# 17.net
KiCad netlist of a schematic drawn in Altium Designer
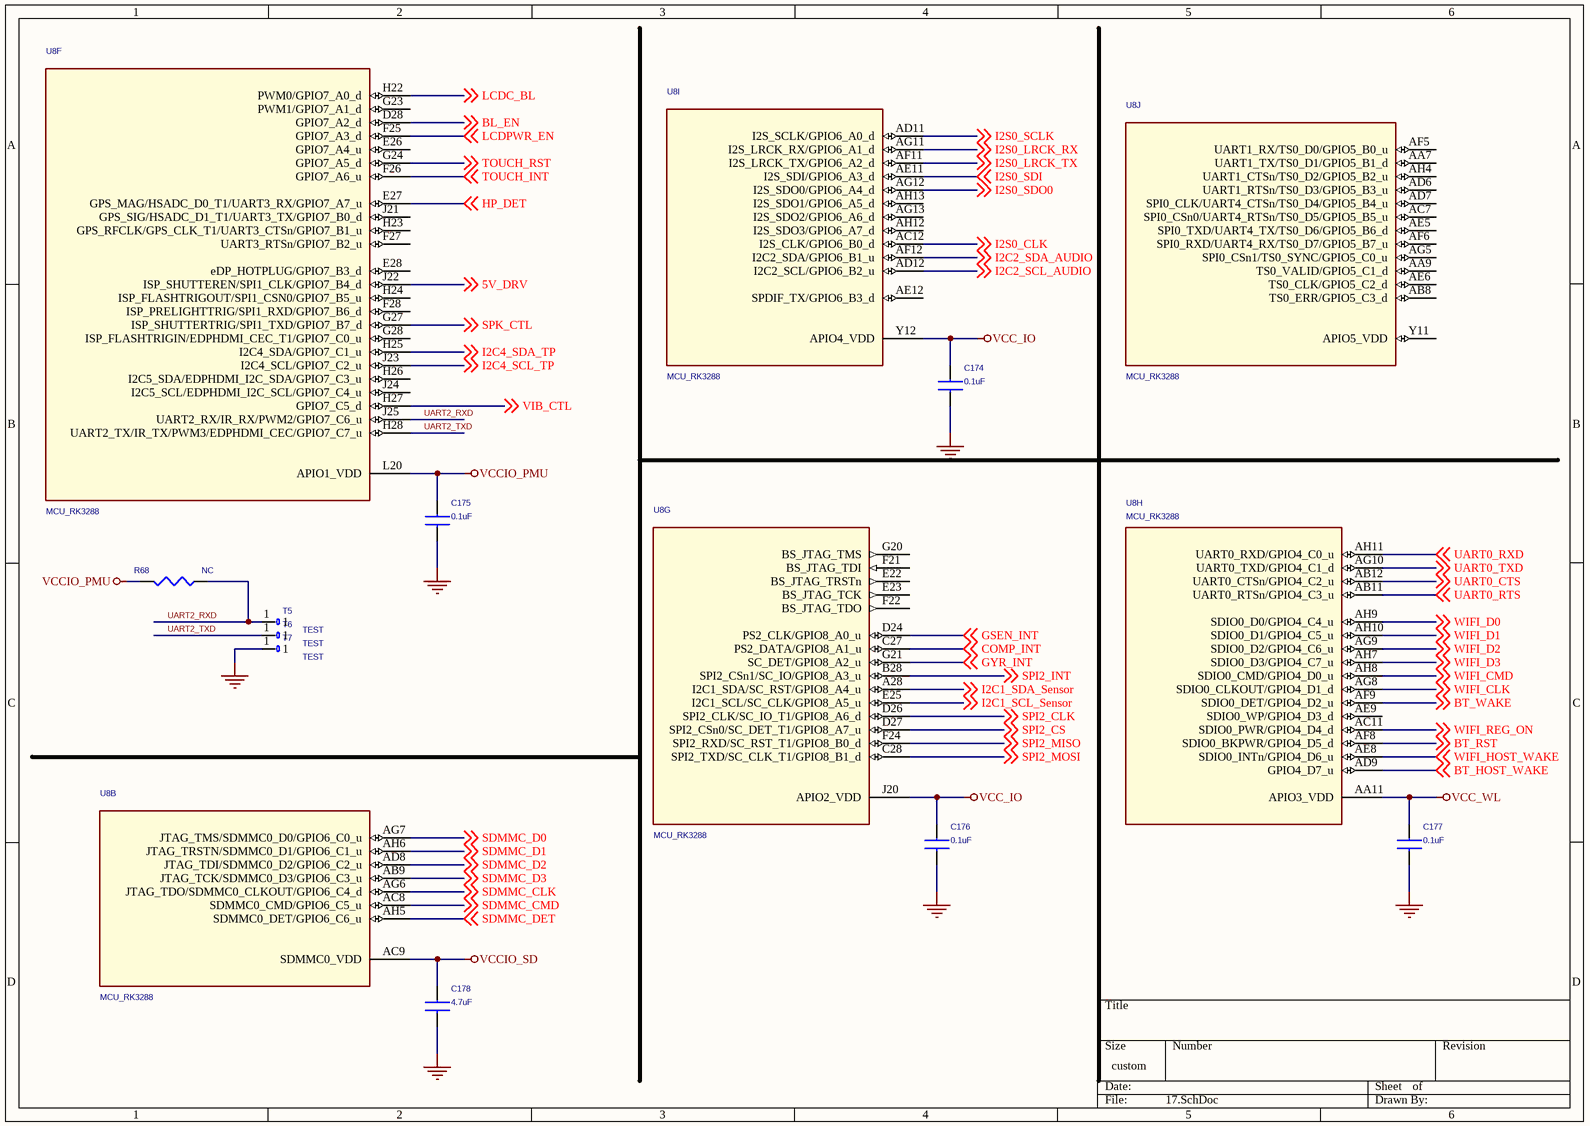
[diagram p0: 17.SchDoc]

(export (version "E")
  (design (tool "Eeschema 10.0.6"))
  (components
    (comp (ref "C174")
      (value "0.1uF")
      (footprint "C0603")
      (description "CAP,MLCC,100nF,+/-10%,X7R,6.3V,SMD0402")
      (libsource (lib "*") (part "CAP NP_Dup3"))
    )
    (comp (ref "C175")
      (value "0.1uF")
      (footprint "C0603")
      (description "CAP,MLCC,100nF,+/-10%,X7R,6.3V,SMD0402")
      (libsource (lib "*") (part "CAP NP_Dup3"))
    )
    (comp (ref "C176") (value "0.1uF") (footprint "C0603") (libsource (lib "*") (part "CAP NP_Dup3")))
    (comp (ref "C177")
      (value "0.1uF")
      (footprint "C0603")
      (description "CAP,MLCC,100nF,+/-10%,X7R,6.3V,SMD0402")
      (libsource (lib "*") (part "CAP NP_Dup3"))
    )
    (comp (ref "C178")
      (value "4.7uF")
      (footprint "C0603")
      (description "CAP,MLCC,100nF,+/-10%,X7R,6.3V,SMD0402")
      (libsource (lib "*") (part "CAP NP_Dup3"))
    )
    (comp (ref "R68")
      (value "NC")
      (footprint "r0402")
      (description "RES,thick film,10KOhm,+/-5%,1/16W,SMD0402")
      (libsource (lib "*") (part "RESISTOR_0_Dup3"))
    )
    (comp (ref "T5") (value "TEST") (footprint "TEST") (libsource (lib "*") (part "TEST_0")))
    (comp (ref "T6") (value "TEST") (footprint "TEST") (libsource (lib "*") (part "TEST_0")))
    (comp (ref "T7") (value "TEST") (footprint "TEST") (libsource (lib "*") (part "TEST_0")))
    (comp (ref "U8")
      (value "MCU_RK3288")
      (footprint "BGA453-19X19")
      (libsource (lib "*") (part "MCU_RK3288_3"))
    )
  )
  (nets
    (net (code "1") (name "/UART2_RXD") (class "Default")
      (node (ref "R68") (pin "1") (pinfunction "1_1") (pintype "passive"))
      (node (ref "T5") (pin "1") (pinfunction "1_1") (pintype "passive"))
      (node (ref "U8") (pin "J25") (pinfunction "UART2_RX/IR_RX/PWM2/GPIO7_C6_u_J25") (pintype "bidirectional"))
    )
    (net (code "2") (name "/UART2_TXD") (class "Default")
      (node (ref "T6") (pin "1") (pinfunction "1_1") (pintype "passive"))
      (node (ref "U8") (pin "H28") (pinfunction "UART2_TX/IR_TX/PWM3/EDPHDMI_CEC/GPIO7_C7_u_H28") (pintype "bidirectional"))
    )
    (net (code "3") (name "5V_DRV") (class "Default")
      (node (ref "U8") (pin "J22") (pinfunction "ISP_SHUTTEREN/SPI1_CLK/GPIO7_B4_d_J22") (pintype "bidirectional"))
    )
    (net (code "4") (name "BL_EN") (class "Default")
      (node (ref "U8") (pin "D28") (pinfunction "GPIO7_A2_d_D28") (pintype "bidirectional"))
    )
    (net (code "5") (name "BT_HOST_WAKE") (class "Default")
      (node (ref "U8") (pin "AD9") (pinfunction "GPIO4_D7_u_AD9") (pintype "bidirectional"))
    )
    (net (code "6") (name "BT_RST") (class "Default")
      (node (ref "U8") (pin "AF8") (pinfunction "SDIO0_BKPWR/GPIO4_D5_d_AF8") (pintype "bidirectional"))
    )
    (net (code "7") (name "BT_WAKE") (class "Default")
      (node (ref "U8") (pin "AF9") (pinfunction "SDIO0_DET/GPIO4_D2_u_AF9") (pintype "bidirectional"))
    )
    (net (code "8") (name "COMP_INT") (class "Default")
      (node (ref "U8") (pin "C27") (pinfunction "PS2_DATA/GPIO8_A1_u_C27") (pintype "bidirectional"))
    )
    (net (code "9") (name "GND") (class "Default")
      (node (ref "C174") (pin "1") (pinfunction "1_1") (pintype "passive"))
      (node (ref "C175") (pin "1") (pinfunction "1_1") (pintype "passive"))
      (node (ref "C176") (pin "2") (pinfunction "2_2") (pintype "passive"))
      (node (ref "C177") (pin "1") (pinfunction "1_1") (pintype "passive"))
      (node (ref "C178") (pin "2") (pinfunction "2_2") (pintype "passive"))
      (node (ref "T7") (pin "1") (pinfunction "1_1") (pintype "passive"))
    )
    (net (code "10") (name "GSEN_INT") (class "Default")
      (node (ref "U8") (pin "D24") (pinfunction "PS2_CLK/GPIO8_A0_u_D24") (pintype "bidirectional"))
    )
    (net (code "11") (name "GYR_INT") (class "Default")
      (node (ref "U8") (pin "G21") (pinfunction "SC_DET/GPIO8_A2_u_G21") (pintype "bidirectional"))
    )
    (net (code "12") (name "HP_DET") (class "Default")
      (node (ref "U8") (pin "E27") (pinfunction "GPS_MAG/HSADC_D0_T1/UART3_RX/GPIO7_A7_u_E27") (pintype "bidirectional"))
    )
    (net (code "13") (name "I2C1_SCL_Sensor") (class "Default")
      (node (ref "U8") (pin "E25") (pinfunction "I2C1_SCL/SC_CLK/GPIO8_A5_u_E25") (pintype "bidirectional"))
    )
    (net (code "14") (name "I2C1_SDA_Sensor") (class "Default")
      (node (ref "U8") (pin "A28") (pinfunction "I2C1_SDA/SC_RST/GPIO8_A4_u_A28") (pintype "bidirectional"))
    )
    (net (code "15") (name "I2C2_SCL_AUDIO") (class "Default")
      (node (ref "U8") (pin "AD12") (pinfunction "I2C2_SCL/GPIO6_B2_u_AD12") (pintype "bidirectional"))
    )
    (net (code "16") (name "I2C2_SDA_AUDIO") (class "Default")
      (node (ref "U8") (pin "AF12") (pinfunction "I2C2_SDA/GPIO6_B1_u_AF12") (pintype "bidirectional"))
    )
    (net (code "17") (name "I2C4_SCL_TP") (class "Default")
      (node (ref "U8") (pin "J23") (pinfunction "I2C4_SCL/GPIO7_C2_u_J23") (pintype "bidirectional"))
    )
    (net (code "18") (name "I2C4_SDA_TP") (class "Default")
      (node (ref "U8") (pin "H25") (pinfunction "I2C4_SDA/GPIO7_C1_u_H25") (pintype "bidirectional"))
    )
    (net (code "19") (name "I2S0_CLK") (class "Default")
      (node (ref "U8") (pin "AC12") (pinfunction "I2S_CLK/GPIO6_B0_d_AC12") (pintype "bidirectional"))
    )
    (net (code "20") (name "I2S0_LRCK_RX") (class "Default")
      (node (ref "U8") (pin "AG11") (pinfunction "I2S_LRCK_RX/GPIO6_A1_d_AG11") (pintype "bidirectional"))
    )
    (net (code "21") (name "I2S0_LRCK_TX") (class "Default")
      (node (ref "U8") (pin "AF11") (pinfunction "I2S_LRCK_TX/GPIO6_A2_d_AF11") (pintype "bidirectional"))
    )
    (net (code "22") (name "I2S0_SCLK") (class "Default")
      (node (ref "U8") (pin "AD11") (pinfunction "I2S_SCLK/GPIO6_A0_d_AD11") (pintype "bidirectional"))
    )
    (net (code "23") (name "I2S0_SDI") (class "Default")
      (node (ref "U8") (pin "AE11") (pinfunction "I2S_SDI/GPIO6_A3_d_AE11") (pintype "bidirectional"))
    )
    (net (code "24") (name "I2S0_SDO0") (class "Default")
      (node (ref "U8") (pin "AG12") (pinfunction "I2S_SDO0/GPIO6_A4_d_AG12") (pintype "bidirectional"))
    )
    (net (code "25") (name "LCDC_BL") (class "Default")
      (node (ref "U8") (pin "H22") (pinfunction "PWM0/GPIO7_A0_d_H22") (pintype "bidirectional"))
    )
    (net (code "26") (name "LCDPWR_EN") (class "Default")
      (node (ref "U8") (pin "F25") (pinfunction "GPIO7_A3_d_F25") (pintype "bidirectional"))
    )
    (net (code "27") (name "SDMMC_CLK") (class "Default")
      (node (ref "U8") (pin "AG6") (pinfunction "JTAG_TDO/SDMMC0_CLKOUT/GPIO6_C4_d_AG6") (pintype "bidirectional"))
    )
    (net (code "28") (name "SDMMC_CMD") (class "Default")
      (node (ref "U8") (pin "AC8") (pinfunction "SDMMC0_CMD/GPIO6_C5_u_AC8") (pintype "bidirectional"))
    )
    (net (code "29") (name "SDMMC_D0") (class "Default")
      (node (ref "U8") (pin "AG7") (pinfunction "JTAG_TMS/SDMMC0_D0/GPIO6_C0_u_AG7") (pintype "bidirectional"))
    )
    (net (code "30") (name "SDMMC_D1") (class "Default")
      (node (ref "U8") (pin "AH6") (pinfunction "JTAG_TRSTN/SDMMC0_D1/GPIO6_C1_u_AH6") (pintype "bidirectional"))
    )
    (net (code "31") (name "SDMMC_D2") (class "Default")
      (node (ref "U8") (pin "AD8") (pinfunction "JTAG_TDI/SDMMC0_D2/GPIO6_C2_u_AD8") (pintype "bidirectional"))
    )
    (net (code "32") (name "SDMMC_D3") (class "Default")
      (node (ref "U8") (pin "AB9") (pinfunction "JTAG_TCK/SDMMC0_D3/GPIO6_C3_u_AB9") (pintype "bidirectional"))
    )
    (net (code "33") (name "SDMMC_DET") (class "Default")
      (node (ref "U8") (pin "AH5") (pinfunction "SDMMC0_DET/GPIO6_C6_u_AH5") (pintype "bidirectional"))
    )
    (net (code "34") (name "SPI2_CLK") (class "Default")
      (node (ref "U8") (pin "D26") (pinfunction "SPI2_CLK/SC_IO_T1/GPIO8_A6_d_D26") (pintype "bidirectional"))
    )
    (net (code "35") (name "SPI2_CS") (class "Default")
      (node (ref "U8") (pin "D27") (pinfunction "SPI2_CSn0/SC_DET_T1/GPIO8_A7_u_D27") (pintype "bidirectional"))
    )
    (net (code "36") (name "SPI2_INT") (class "Default")
      (node (ref "U8") (pin "B28") (pinfunction "SPI2_CSn1/SC_IO/GPIO8_A3_u_B28") (pintype "bidirectional"))
    )
    (net (code "37") (name "SPI2_MISO") (class "Default")
      (node (ref "U8") (pin "F24") (pinfunction "SPI2_RXD/SC_RST_T1/GPIO8_B0_d_F24") (pintype "bidirectional"))
    )
    (net (code "38") (name "SPI2_MOSI") (class "Default")
      (node (ref "U8") (pin "C28") (pinfunction "SPI2_TXD/SC_CLK_T1/GPIO8_B1_d_C28") (pintype "bidirectional"))
    )
    (net (code "39") (name "SPK_CTL") (class "Default")
      (node (ref "U8") (pin "G27") (pinfunction "ISP_SHUTTERTRIG/SPI1_TXD/GPIO7_B7_d_G27") (pintype "bidirectional"))
    )
    (net (code "40") (name "TOUCH_INT") (class "Default")
      (node (ref "U8") (pin "F26") (pinfunction "GPIO7_A6_u_F26") (pintype "bidirectional"))
    )
    (net (code "41") (name "TOUCH_RST") (class "Default")
      (node (ref "U8") (pin "G24") (pinfunction "GPIO7_A5_d_G24") (pintype "bidirectional"))
    )
    (net (code "42") (name "UART0_CTS") (class "Default")
      (node (ref "U8") (pin "AB12") (pinfunction "UART0_CTSn/GPIO4_C2_u_AB12") (pintype "bidirectional"))
    )
    (net (code "43") (name "UART0_RTS") (class "Default")
      (node (ref "U8") (pin "AB11") (pinfunction "UART0_RTSn/GPIO4_C3_u_AB11") (pintype "bidirectional"))
    )
    (net (code "44") (name "UART0_RXD") (class "Default")
      (node (ref "U8") (pin "AH11") (pinfunction "UART0_RXD/GPIO4_C0_u_AH11") (pintype "bidirectional"))
    )
    (net (code "45") (name "UART0_TXD") (class "Default")
      (node (ref "U8") (pin "AG10") (pinfunction "UART0_TXD/GPIO4_C1_d_AG10") (pintype "bidirectional"))
    )
    (net (code "46") (name "VCCIO_PMU") (class "Default")
      (node (ref "C175") (pin "2") (pinfunction "2_2") (pintype "passive"))
      (node (ref "R68") (pin "2") (pinfunction "2_2") (pintype "passive"))
      (node (ref "U8") (pin "L20") (pinfunction "APIO1_VDD_L20") (pintype "power_in"))
    )
    (net (code "47") (name "VCCIO_SD") (class "Default")
      (node (ref "C178") (pin "1") (pinfunction "1_1") (pintype "passive"))
      (node (ref "U8") (pin "AC9") (pinfunction "SDMMC0_VDD_AC9") (pintype "power_in"))
    )
    (net (code "48") (name "VCC_IO") (class "Default")
      (node (ref "C174") (pin "2") (pinfunction "2_2") (pintype "passive"))
      (node (ref "C176") (pin "1") (pinfunction "1_1") (pintype "passive"))
      (node (ref "U8") (pin "J20") (pinfunction "APIO2_VDD_J20") (pintype "power_in"))
      (node (ref "U8") (pin "Y12") (pinfunction "APIO4_VDD_Y12") (pintype "power_in"))
    )
    (net (code "49") (name "VCC_WL") (class "Default")
      (node (ref "C177") (pin "2") (pinfunction "2_2") (pintype "passive"))
      (node (ref "U8") (pin "AA11") (pinfunction "APIO3_VDD_AA11") (pintype "power_in"))
    )
    (net (code "50") (name "VIB_CTL") (class "Default")
      (node (ref "U8") (pin "H27") (pinfunction "GPIO7_C5_d_H27") (pintype "bidirectional"))
    )
    (net (code "51") (name "WIFI_CLK") (class "Default")
      (node (ref "U8") (pin "AG8") (pinfunction "SDIO0_CLKOUT/GPIO4_D1_d_AG8") (pintype "bidirectional"))
    )
    (net (code "52") (name "WIFI_CMD") (class "Default")
      (node (ref "U8") (pin "AH8") (pinfunction "SDIO0_CMD/GPIO4_D0_u_AH8") (pintype "bidirectional"))
    )
    (net (code "53") (name "WIFI_D0") (class "Default")
      (node (ref "U8") (pin "AH9") (pinfunction "SDIO0_D0/GPIO4_C4_u_AH9") (pintype "bidirectional"))
    )
    (net (code "54") (name "WIFI_D1") (class "Default")
      (node (ref "U8") (pin "AH10") (pinfunction "SDIO0_D1/GPIO4_C5_u_AH10") (pintype "bidirectional"))
    )
    (net (code "55") (name "WIFI_D2") (class "Default")
      (node (ref "U8") (pin "AG9") (pinfunction "SDIO0_D2/GPIO4_C6_u_AG9") (pintype "bidirectional"))
    )
    (net (code "56") (name "WIFI_D3") (class "Default")
      (node (ref "U8") (pin "AH7") (pinfunction "SDIO0_D3/GPIO4_C7_u_AH7") (pintype "bidirectional"))
    )
    (net (code "57") (name "WIFI_HOST_WAKE") (class "Default")
      (node (ref "U8") (pin "AE8") (pinfunction "SDIO0_INTn/GPIO4_D6_u_AE8") (pintype "bidirectional"))
    )
    (net (code "58") (name "WIFI_REG_ON") (class "Default")
      (node (ref "U8") (pin "AC11") (pinfunction "SDIO0_PWR/GPIO4_D4_d_AC11") (pintype "bidirectional"))
    )
    (net (code "59") (name "unconnected-(U8F-GPIO7_A4_u-PadE26)") (class "Default")
      (node (ref "U8") (pin "E26") (pinfunction "GPIO7_A4_u_E26") (pintype "bidirectional"))
    )
    (net (code "60") (name "unconnected-(U8F-GPS_RFCLK{slash}GPS_CLK_T1{slash}UART3_CTSn{slash}GPIO7_B1_u-PadH23)") (class "Default")
      (node (ref "U8") (pin "H23") (pinfunction "GPS_RFCLK/GPS_CLK_T1/UART3_CTSn/GPIO7_B1_u_H23") (pintype "bidirectional"))
    )
    (net (code "61") (name "unconnected-(U8F-GPS_SIG{slash}HSADC_D1_T1{slash}UART3_TX{slash}GPIO7_B0_d-PadJ21)") (class "Default")
      (node (ref "U8") (pin "J21") (pinfunction "GPS_SIG/HSADC_D1_T1/UART3_TX/GPIO7_B0_d_J21") (pintype "bidirectional"))
    )
    (net (code "62") (name "unconnected-(U8F-I2C5_SCL{slash}EDPHDMI_I2C_SCL{slash}GPIO7_C4_u-PadJ24)") (class "Default")
      (node (ref "U8") (pin "J24") (pinfunction "I2C5_SCL/EDPHDMI_I2C_SCL/GPIO7_C4_u_J24") (pintype "bidirectional"))
    )
    (net (code "63") (name "unconnected-(U8F-I2C5_SDA{slash}EDPHDMI_I2C_SDA{slash}GPIO7_C3_u-PadH26)") (class "Default")
      (node (ref "U8") (pin "H26") (pinfunction "I2C5_SDA/EDPHDMI_I2C_SDA/GPIO7_C3_u_H26") (pintype "bidirectional"))
    )
    (net (code "64") (name "unconnected-(U8F-ISP_FLASHTRIGIN{slash}EDPHDMI_CEC_T1{slash}GPIO7_C0_u-PadG28)") (class "Default")
      (node (ref "U8") (pin "G28") (pinfunction "ISP_FLASHTRIGIN/EDPHDMI_CEC_T1/GPIO7_C0_u_G28") (pintype "bidirectional"))
    )
    (net (code "65") (name "unconnected-(U8F-ISP_FLASHTRIGOUT{slash}SPI1_CSN0{slash}GPIO7_B5_u-PadH24)") (class "Default")
      (node (ref "U8") (pin "H24") (pinfunction "ISP_FLASHTRIGOUT/SPI1_CSN0/GPIO7_B5_u_H24") (pintype "bidirectional"))
    )
    (net (code "66") (name "unconnected-(U8F-ISP_PRELIGHTTRIG{slash}SPI1_RXD{slash}GPIO7_B6_d-PadF28)") (class "Default")
      (node (ref "U8") (pin "F28") (pinfunction "ISP_PRELIGHTTRIG/SPI1_RXD/GPIO7_B6_d_F28") (pintype "bidirectional"))
    )
    (net (code "67") (name "unconnected-(U8F-PWM1{slash}GPIO7_A1_d-PadG23)") (class "Default")
      (node (ref "U8") (pin "G23") (pinfunction "PWM1/GPIO7_A1_d_G23") (pintype "bidirectional"))
    )
    (net (code "68") (name "unconnected-(U8F-UART3_RTSn{slash}GPIO7_B2_u-PadF27)") (class "Default")
      (node (ref "U8") (pin "F27") (pinfunction "UART3_RTSn/GPIO7_B2_u_F27") (pintype "bidirectional"))
    )
    (net (code "69") (name "unconnected-(U8F-eDP_HOTPLUG{slash}GPIO7_B3_d-PadE28)") (class "Default")
      (node (ref "U8") (pin "E28") (pinfunction "eDP_HOTPLUG/GPIO7_B3_d_E28") (pintype "bidirectional"))
    )
    (net (code "70") (name "unconnected-(U8G-BS_JTAG_TCK-PadE23)") (class "Default")
      (node (ref "U8") (pin "E23") (pinfunction "BS_JTAG_TCK_E23") (pintype "output"))
    )
    (net (code "71") (name "unconnected-(U8G-BS_JTAG_TDI-PadF21)") (class "Default")
      (node (ref "U8") (pin "F21") (pinfunction "BS_JTAG_TDI_F21") (pintype "input"))
    )
    (net (code "72") (name "unconnected-(U8G-BS_JTAG_TDO-PadF22)") (class "Default")
      (node (ref "U8") (pin "F22") (pinfunction "BS_JTAG_TDO_F22") (pintype "output"))
    )
    (net (code "73") (name "unconnected-(U8G-BS_JTAG_TMS-PadG20)") (class "Default")
      (node (ref "U8") (pin "G20") (pinfunction "BS_JTAG_TMS_G20") (pintype "output"))
    )
    (net (code "74") (name "unconnected-(U8G-BS_JTAG_TRSTn-PadE22)") (class "Default")
      (node (ref "U8") (pin "E22") (pinfunction "BS_JTAG_TRSTn_E22") (pintype "output"))
    )
    (net (code "75") (name "unconnected-(U8H-SDIO0_WP{slash}GPIO4_D3_d-PadAE9)") (class "Default")
      (node (ref "U8") (pin "AE9") (pinfunction "SDIO0_WP/GPIO4_D3_d_AE9") (pintype "bidirectional"))
    )
    (net (code "76") (name "unconnected-(U8I-I2S_SDO1{slash}GPIO6_A5_d-PadAH13)") (class "Default")
      (node (ref "U8") (pin "AH13") (pinfunction "I2S_SDO1/GPIO6_A5_d_AH13") (pintype "bidirectional"))
    )
    (net (code "77") (name "unconnected-(U8I-I2S_SDO2{slash}GPIO6_A6_d-PadAG13)") (class "Default")
      (node (ref "U8") (pin "AG13") (pinfunction "I2S_SDO2/GPIO6_A6_d_AG13") (pintype "bidirectional"))
    )
    (net (code "78") (name "unconnected-(U8I-I2S_SDO3{slash}GPIO6_A7_d-PadAH12)") (class "Default")
      (node (ref "U8") (pin "AH12") (pinfunction "I2S_SDO3/GPIO6_A7_d_AH12") (pintype "bidirectional"))
    )
    (net (code "79") (name "unconnected-(U8I-SPDIF_TX{slash}GPIO6_B3_d-PadAE12)") (class "Default")
      (node (ref "U8") (pin "AE12") (pinfunction "SPDIF_TX/GPIO6_B3_d_AE12") (pintype "bidirectional"))
    )
    (net (code "80") (name "unconnected-(U8J-APIO5_VDD-PadY11)") (class "Default")
      (node (ref "U8") (pin "Y11") (pinfunction "APIO5_VDD_Y11") (pintype "bidirectional"))
    )
    (net (code "81") (name "unconnected-(U8J-SPI0_CLK{slash}UART4_CTSn{slash}TS0_D4{slash}GPIO5_B4_u-PadAD7)") (class "Default")
      (node (ref "U8") (pin "AD7") (pinfunction "SPI0_CLK/UART4_CTSn/TS0_D4/GPIO5_B4_u_AD7") (pintype "bidirectional"))
    )
    (net (code "82") (name "unconnected-(U8J-SPI0_CSn0{slash}UART4_RTSn{slash}TS0_D5{slash}GPIO5_B5_u-PadAC7)") (class "Default")
      (node (ref "U8") (pin "AC7") (pinfunction "SPI0_CSn0/UART4_RTSn/TS0_D5/GPIO5_B5_u_AC7") (pintype "bidirectional"))
    )
    (net (code "83") (name "unconnected-(U8J-SPI0_CSn1{slash}TS0_SYNC{slash}GPIO5_C0_u-PadAG5)") (class "Default")
      (node (ref "U8") (pin "AG5") (pinfunction "SPI0_CSn1/TS0_SYNC/GPIO5_C0_u_AG5") (pintype "bidirectional"))
    )
    (net (code "84") (name "unconnected-(U8J-SPI0_RXD{slash}UART4_RX{slash}TS0_D7{slash}GPIO5_B7_u-PadAF6)") (class "Default")
      (node (ref "U8") (pin "AF6") (pinfunction "SPI0_RXD/UART4_RX/TS0_D7/GPIO5_B7_u_AF6") (pintype "bidirectional"))
    )
    (net (code "85") (name "unconnected-(U8J-SPI0_TXD{slash}UART4_TX{slash}TS0_D6{slash}GPIO5_B6_d-PadAE5)") (class "Default")
      (node (ref "U8") (pin "AE5") (pinfunction "SPI0_TXD/UART4_TX/TS0_D6/GPIO5_B6_d_AE5") (pintype "bidirectional"))
    )
    (net (code "86") (name "unconnected-(U8J-TS0_CLK{slash}GPIO5_C2_d-PadAE6)") (class "Default")
      (node (ref "U8") (pin "AE6") (pinfunction "TS0_CLK/GPIO5_C2_d_AE6") (pintype "bidirectional"))
    )
    (net (code "87") (name "unconnected-(U8J-TS0_ERR{slash}GPIO5_C3_d-PadAB8)") (class "Default")
      (node (ref "U8") (pin "AB8") (pinfunction "TS0_ERR/GPIO5_C3_d_AB8") (pintype "bidirectional"))
    )
    (net (code "88") (name "unconnected-(U8J-TS0_VALID{slash}GPIO5_C1_d-PadAA9)") (class "Default")
      (node (ref "U8") (pin "AA9") (pinfunction "TS0_VALID/GPIO5_C1_d_AA9") (pintype "bidirectional"))
    )
    (net (code "89") (name "unconnected-(U8J-UART1_CTSn{slash}TS0_D2{slash}GPIO5_B2_u-PadAH4)") (class "Default")
      (node (ref "U8") (pin "AH4") (pinfunction "UART1_CTSn/TS0_D2/GPIO5_B2_u_AH4") (pintype "bidirectional"))
    )
    (net (code "90") (name "unconnected-(U8J-UART1_RTSn{slash}TS0_D3{slash}GPIO5_B3_u-PadAD6)") (class "Default")
      (node (ref "U8") (pin "AD6") (pinfunction "UART1_RTSn/TS0_D3/GPIO5_B3_u_AD6") (pintype "bidirectional"))
    )
    (net (code "91") (name "unconnected-(U8J-UART1_RX{slash}TS0_D0{slash}GPIO5_B0_u-PadAF5)") (class "Default")
      (node (ref "U8") (pin "AF5") (pinfunction "UART1_RX/TS0_D0/GPIO5_B0_u_AF5") (pintype "bidirectional"))
    )
    (net (code "92") (name "unconnected-(U8J-UART1_TX{slash}TS0_D1{slash}GPIO5_B1_d-PadAA7)") (class "Default")
      (node (ref "U8") (pin "AA7") (pinfunction "UART1_TX/TS0_D1/GPIO5_B1_d_AA7") (pintype "bidirectional"))
    )
  )
)
